# MaxAir_Smart_Home_Gateway_WT21-ET01-v095.net
KiCad netlist of a schematic drawn in EAGLE
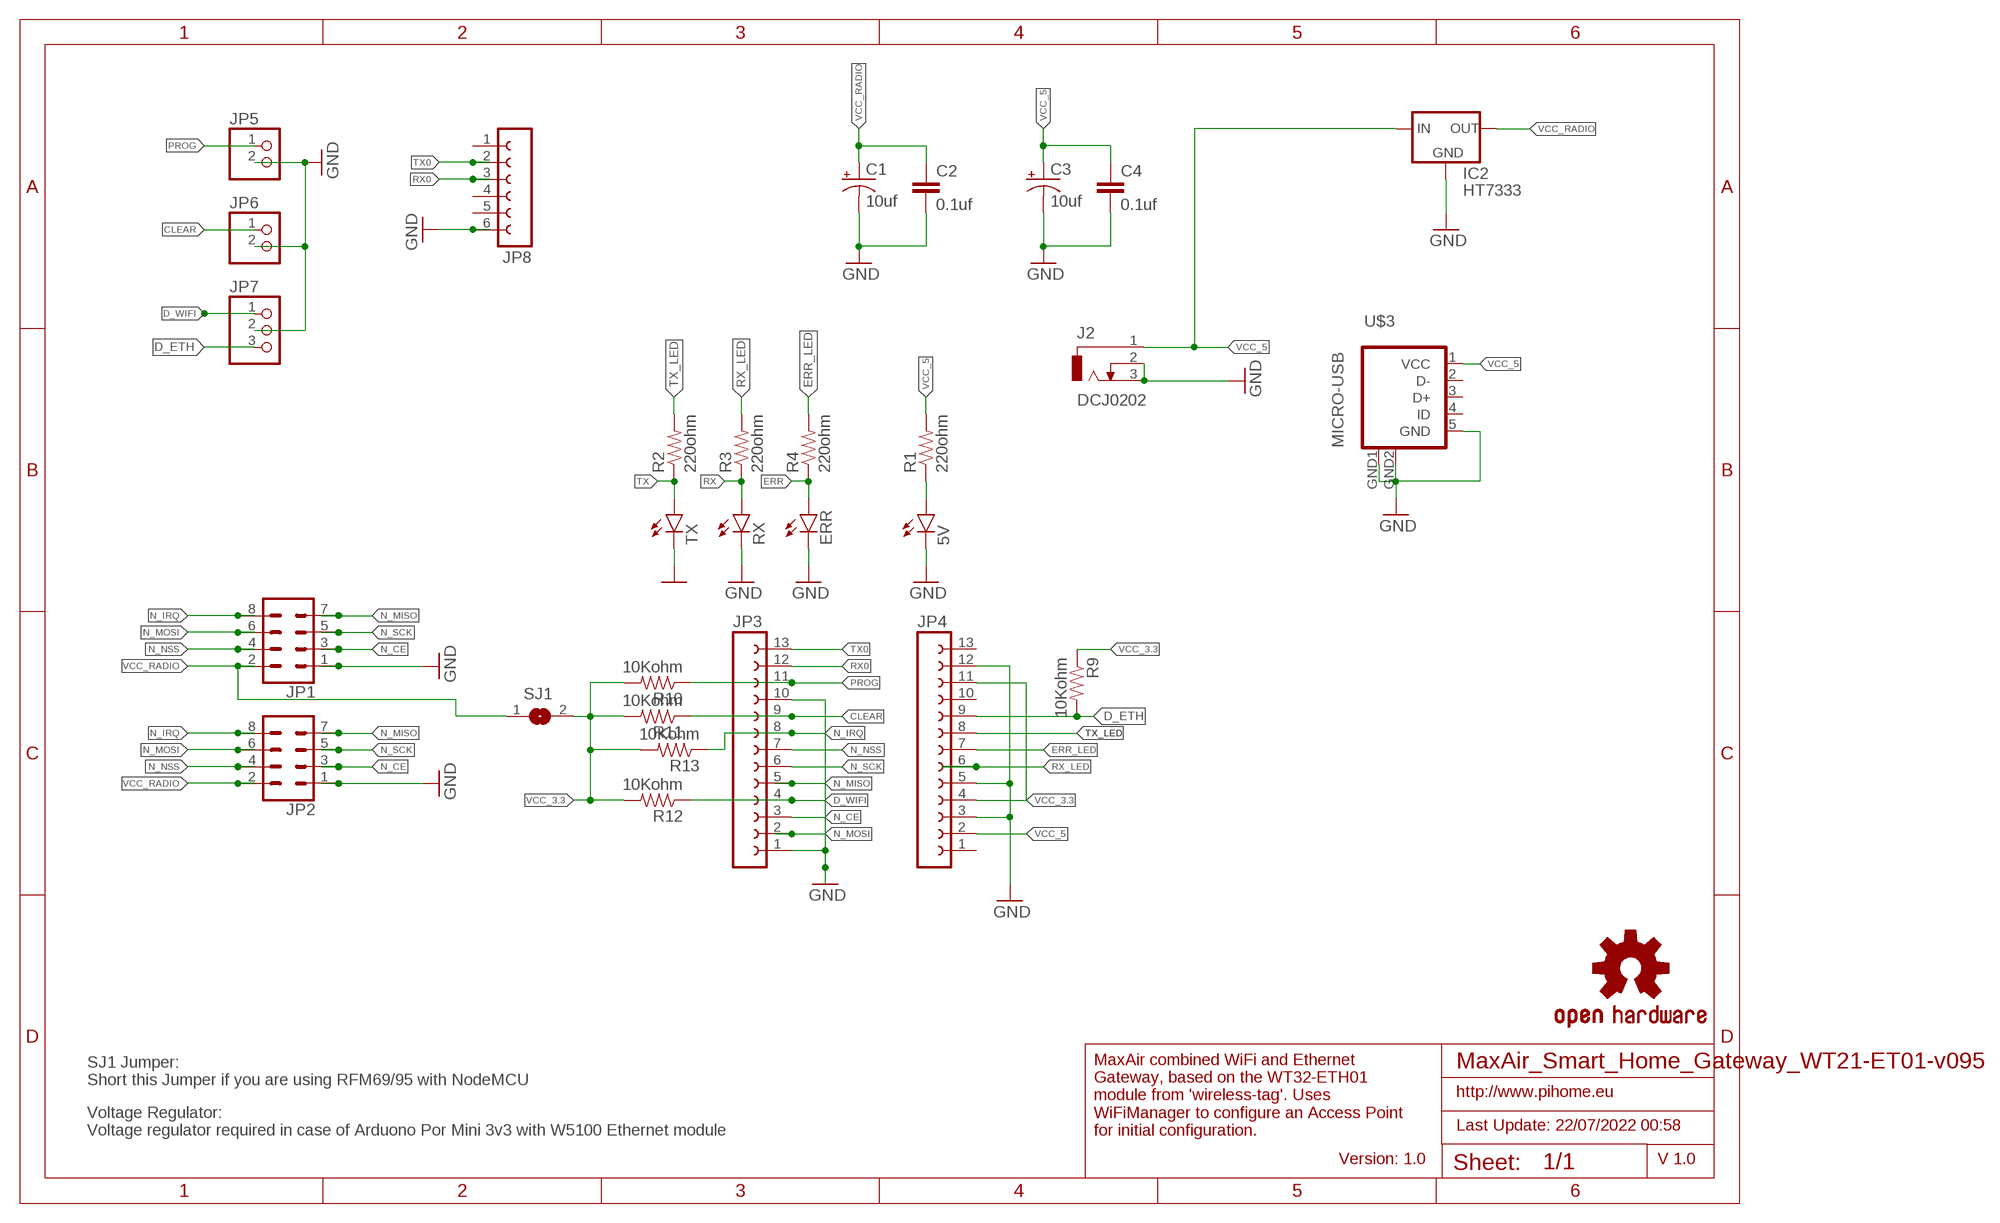
[diagram p0: schematic, sheet 1]

(export (version "E")
  (design (tool "Eeschema 10.0.6"))
  (components
    (comp (ref "5V")
      (value "LED3MM")
      (footprint "eagle-import:LED3MM")
      (libsource (lib "eagle-import") (part "LED3MM"))
    )
    (comp (ref "C1")
      (value "10uf")
      (footprint "eagle-import:CPOL-RADIAL-10UF-25V-KIT")
      (libsource (lib "eagle-import") (part "10UF-25V-20%(PTH)KIT"))
    )
    (comp (ref "C2")
      (value "0.1uf")
      (footprint "eagle-import:CAP-PTH-SMALL-KIT")
      (libsource (lib "eagle-import") (part "0.1UF-50V-20%(PTH)KIT-EZ"))
    )
    (comp (ref "C3")
      (value "10uf")
      (footprint "eagle-import:CPOL-RADIAL-10UF-25V-KIT")
      (libsource (lib "eagle-import") (part "10UF-25V-20%(PTH)KIT"))
    )
    (comp (ref "C4")
      (value "0.1uf")
      (footprint "eagle-import:CAP-PTH-SMALL-KIT")
      (libsource (lib "eagle-import") (part "0.1UF-50V-20%(PTH)KIT-EZ"))
    )
    (comp (ref "ERR")
      (value "LED3MM")
      (footprint "eagle-import:LED3MM")
      (libsource (lib "eagle-import") (part "LED3MM"))
    )
    (comp (ref "IC2")
      (value "HT7333")
      (footprint "eagle-import:SOT-89")
      (libsource (lib "eagle-import") (part "HT7333"))
    )
    (comp (ref "J2")
      (value "DCJ0202")
      (footprint "eagle-import:DCJ0202")
      (libsource (lib "eagle-import") (part "DCJ0202"))
    )
    (comp (ref "JP1")
      (value "CONN_04X2")
      (footprint "eagle-import:2X4")
      (libsource (lib "eagle-import") (part "CONN_04X2"))
    )
    (comp (ref "JP2")
      (value "CONN_04X2")
      (footprint "eagle-import:2X4")
      (libsource (lib "eagle-import") (part "CONN_04X2"))
    )
    (comp (ref "JP3")
      (value "FE13-1")
      (footprint "eagle-import:FE13")
      (libsource (lib "eagle-import") (part "FE13-1"))
    )
    (comp (ref "JP4")
      (value "FE13-1")
      (footprint "eagle-import:FE13")
      (libsource (lib "eagle-import") (part "FE13-1"))
    )
    (comp (ref "JP5")
      (value "PINHD-1X2")
      (footprint "eagle-import:1X02")
      (libsource (lib "eagle-import") (part "PINHD-1X2"))
    )
    (comp (ref "JP6")
      (value "PINHD-1X2")
      (footprint "eagle-import:1X02")
      (libsource (lib "eagle-import") (part "PINHD-1X2"))
    )
    (comp (ref "JP7")
      (value "PINHD-1X3")
      (footprint "eagle-import:1X03")
      (libsource (lib "eagle-import") (part "PINHD-1X3"))
    )
    (comp (ref "JP8")
      (value "FE06-1")
      (footprint "eagle-import:FE06")
      (libsource (lib "eagle-import") (part "FE06-1"))
    )
    (comp (ref "LOGO1")
      (value "OSHW-LOGOMINI")
      (footprint "eagle-import:OSHW-LOGO-MINI")
      (libsource (lib "eagle-import") (part "OSHW-LOGOMINI"))
    )
    (comp (ref "R1")
      (value "220ohm")
      (footprint "eagle-import:AXIAL-0.3")
      (libsource (lib "eagle-import") (part "RESISTORAXIAL-0.3"))
    )
    (comp (ref "R2")
      (value "220ohm")
      (footprint "eagle-import:AXIAL-0.3")
      (libsource (lib "eagle-import") (part "RESISTORAXIAL-0.3"))
    )
    (comp (ref "R3")
      (value "220ohm")
      (footprint "eagle-import:AXIAL-0.3")
      (libsource (lib "eagle-import") (part "RESISTORAXIAL-0.3"))
    )
    (comp (ref "R4")
      (value "220ohm")
      (footprint "eagle-import:AXIAL-0.3")
      (libsource (lib "eagle-import") (part "RESISTORAXIAL-0.3"))
    )
    (comp (ref "R9")
      (value "10Kohm")
      (footprint "eagle-import:AXIAL-0.3")
      (libsource (lib "eagle-import") (part "RESISTORAXIAL-0.3"))
    )
    (comp (ref "R10")
      (value "10Kohm")
      (footprint "eagle-import:AXIAL-0.3")
      (libsource (lib "eagle-import") (part "RESISTORAXIAL-0.3"))
    )
    (comp (ref "R11")
      (value "10Kohm")
      (footprint "eagle-import:AXIAL-0.3")
      (libsource (lib "eagle-import") (part "RESISTORAXIAL-0.3"))
    )
    (comp (ref "R12")
      (value "10Kohm")
      (footprint "eagle-import:AXIAL-0.3")
      (libsource (lib "eagle-import") (part "RESISTORAXIAL-0.3"))
    )
    (comp (ref "R13")
      (value "10Kohm")
      (footprint "eagle-import:AXIAL-0.3")
      (libsource (lib "eagle-import") (part "RESISTORAXIAL-0.3"))
    )
    (comp (ref "RX")
      (value "LED3MM")
      (footprint "eagle-import:LED3MM")
      (libsource (lib "eagle-import") (part "LED3MM"))
    )
    (comp (ref "SJ1") (value "SJ") (footprint "eagle-import:SJ") (libsource (lib "eagle-import") (part "SJ")))
    (comp (ref "TX")
      (value "LED3MM")
      (footprint "eagle-import:LED3MM")
      (libsource (lib "eagle-import") (part "LED3MM"))
    )
    (comp (ref "U$3")
      (value "MICRO-USB")
      (footprint "eagle-import:MICRO-USB")
      (libsource (lib "eagle-import") (part "MICRO-USB"))
    )
  )
  (nets
    (net (code "1") (name "CLEAR") (class "Default")
      (node (ref "JP3") (pin "9") (pinfunction "9_9") (pintype "passive"))
      (node (ref "JP6") (pin "1") (pinfunction "1_1") (pintype "passive"))
      (node (ref "R11") (pin "P$1") (pinfunction "1_P$1") (pintype "passive"))
    )
    (net (code "2") (name "D_ETH") (class "Default")
      (node (ref "JP4") (pin "9") (pinfunction "9_9") (pintype "passive"))
      (node (ref "JP7") (pin "3") (pinfunction "3_3") (pintype "passive"))
      (node (ref "R9") (pin "P$2") (pinfunction "2_P$2") (pintype "passive"))
    )
    (net (code "3") (name "D_WIFI") (class "Default")
      (node (ref "JP3") (pin "4") (pinfunction "4_4") (pintype "passive"))
      (node (ref "JP7") (pin "1") (pinfunction "1_1") (pintype "passive"))
      (node (ref "R12") (pin "P$1") (pinfunction "1_P$1") (pintype "passive"))
    )
    (net (code "4") (name "ERR") (class "Default")
      (node (ref "ERR") (pin "A") (pinfunction "A_A") (pintype "passive"))
      (node (ref "R4") (pin "P$1") (pinfunction "1_P$1") (pintype "passive"))
    )
    (net (code "5") (name "ERR_LED") (class "Default")
      (node (ref "JP4") (pin "7") (pinfunction "7_7") (pintype "passive"))
      (node (ref "R4") (pin "P$2") (pinfunction "2_P$2") (pintype "passive"))
    )
    (net (code "6") (name "GND") (class "Default")
      (node (ref "5V") (pin "K") (pinfunction "C_K") (pintype "passive"))
      (node (ref "C1") (pin "2") (pinfunction "-_2") (pintype "passive"))
      (node (ref "C2") (pin "2") (pinfunction "2_2") (pintype "passive"))
      (node (ref "C3") (pin "2") (pinfunction "-_2") (pintype "passive"))
      (node (ref "C4") (pin "2") (pinfunction "2_2") (pintype "passive"))
      (node (ref "ERR") (pin "K") (pinfunction "C_K") (pintype "passive"))
      (node (ref "IC2") (pin "2") (pinfunction "GND_2") (pintype "input"))
      (node (ref "J2") (pin "2") (pinfunction "2_2") (pintype "passive"))
      (node (ref "J2") (pin "3") (pinfunction "3_3") (pintype "passive"))
      (node (ref "JP1") (pin "1") (pinfunction "1_1") (pintype "passive"))
      (node (ref "JP2") (pin "1") (pinfunction "1_1") (pintype "passive"))
      (node (ref "JP3") (pin "1") (pinfunction "1_1") (pintype "passive"))
      (node (ref "JP3") (pin "10") (pinfunction "10_10") (pintype "passive"))
      (node (ref "JP4") (pin "12") (pinfunction "12_12") (pintype "passive"))
      (node (ref "JP4") (pin "3") (pinfunction "3_3") (pintype "passive"))
      (node (ref "JP4") (pin "5") (pinfunction "5_5") (pintype "passive"))
      (node (ref "JP5") (pin "2") (pinfunction "2_2") (pintype "passive"))
      (node (ref "JP6") (pin "2") (pinfunction "2_2") (pintype "passive"))
      (node (ref "JP7") (pin "2") (pinfunction "2_2") (pintype "passive"))
      (node (ref "JP8") (pin "6") (pinfunction "6_6") (pintype "passive"))
      (node (ref "RX") (pin "K") (pinfunction "C_K") (pintype "passive"))
      (node (ref "TX") (pin "K") (pinfunction "C_K") (pintype "passive"))
      (node (ref "U$3") (pin "5") (pinfunction "GND_5") (pintype "power_in"))
      (node (ref "U$3") (pin "GND1") (pinfunction "GND_GND1") (pintype "power_in"))
      (node (ref "U$3") (pin "GND2") (pinfunction "GND_GND2") (pintype "power_in"))
    )
    (net (code "7") (name "N_CE") (class "Default")
      (node (ref "JP1") (pin "3") (pinfunction "3_3") (pintype "passive"))
      (node (ref "JP2") (pin "3") (pinfunction "3_3") (pintype "passive"))
      (node (ref "JP3") (pin "3") (pinfunction "3_3") (pintype "passive"))
    )
    (net (code "8") (name "N_IRQ") (class "Default")
      (node (ref "JP1") (pin "8") (pinfunction "8_8") (pintype "passive"))
      (node (ref "JP2") (pin "8") (pinfunction "8_8") (pintype "passive"))
      (node (ref "JP3") (pin "8") (pinfunction "8_8") (pintype "passive"))
      (node (ref "R13") (pin "P$1") (pinfunction "1_P$1") (pintype "passive"))
    )
    (net (code "9") (name "N_MISO") (class "Default")
      (node (ref "JP1") (pin "7") (pinfunction "7_7") (pintype "passive"))
      (node (ref "JP2") (pin "7") (pinfunction "7_7") (pintype "passive"))
      (node (ref "JP3") (pin "5") (pinfunction "5_5") (pintype "passive"))
    )
    (net (code "10") (name "N_MOSI") (class "Default")
      (node (ref "JP1") (pin "6") (pinfunction "6_6") (pintype "passive"))
      (node (ref "JP2") (pin "6") (pinfunction "6_6") (pintype "passive"))
      (node (ref "JP3") (pin "2") (pinfunction "2_2") (pintype "passive"))
    )
    (net (code "11") (name "N_NSS") (class "Default")
      (node (ref "JP1") (pin "4") (pinfunction "4_4") (pintype "passive"))
      (node (ref "JP2") (pin "4") (pinfunction "4_4") (pintype "passive"))
      (node (ref "JP3") (pin "7") (pinfunction "7_7") (pintype "passive"))
    )
    (net (code "12") (name "N_SCK") (class "Default")
      (node (ref "JP1") (pin "5") (pinfunction "5_5") (pintype "passive"))
      (node (ref "JP2") (pin "5") (pinfunction "5_5") (pintype "passive"))
      (node (ref "JP3") (pin "6") (pinfunction "6_6") (pintype "passive"))
    )
    (net (code "13") (name "Net-(R1-1)") (class "Default")
      (node (ref "5V") (pin "A") (pinfunction "A_A") (pintype "passive"))
      (node (ref "R1") (pin "P$1") (pinfunction "1_P$1") (pintype "passive"))
    )
    (net (code "14") (name "PROG") (class "Default")
      (node (ref "JP3") (pin "11") (pinfunction "11_11") (pintype "passive"))
      (node (ref "JP5") (pin "1") (pinfunction "1_1") (pintype "passive"))
      (node (ref "R10") (pin "P$1") (pinfunction "1_P$1") (pintype "passive"))
    )
    (net (code "15") (name "RX") (class "Default")
      (node (ref "R3") (pin "P$1") (pinfunction "1_P$1") (pintype "passive"))
      (node (ref "RX") (pin "A") (pinfunction "A_A") (pintype "passive"))
    )
    (net (code "16") (name "RX0") (class "Default")
      (node (ref "JP3") (pin "12") (pinfunction "12_12") (pintype "passive"))
      (node (ref "JP8") (pin "3") (pinfunction "3_3") (pintype "passive"))
    )
    (net (code "17") (name "RX_LED") (class "Default")
      (node (ref "JP4") (pin "6") (pinfunction "6_6") (pintype "passive"))
      (node (ref "R3") (pin "P$2") (pinfunction "2_P$2") (pintype "passive"))
    )
    (net (code "18") (name "TX") (class "Default")
      (node (ref "R2") (pin "P$1") (pinfunction "1_P$1") (pintype "passive"))
      (node (ref "TX") (pin "A") (pinfunction "A_A") (pintype "passive"))
    )
    (net (code "19") (name "TX0") (class "Default")
      (node (ref "JP3") (pin "13") (pinfunction "13_13") (pintype "passive"))
      (node (ref "JP8") (pin "2") (pinfunction "2_2") (pintype "passive"))
    )
    (net (code "20") (name "TX_LED") (class "Default")
      (node (ref "JP4") (pin "8") (pinfunction "8_8") (pintype "passive"))
      (node (ref "R2") (pin "P$2") (pinfunction "2_P$2") (pintype "passive"))
    )
    (net (code "21") (name "VCC_3.3") (class "Default")
      (node (ref "JP4") (pin "11") (pinfunction "11_11") (pintype "passive"))
      (node (ref "JP4") (pin "4") (pinfunction "4_4") (pintype "passive"))
      (node (ref "R10") (pin "P$2") (pinfunction "2_P$2") (pintype "passive"))
      (node (ref "R11") (pin "P$2") (pinfunction "2_P$2") (pintype "passive"))
      (node (ref "R12") (pin "P$2") (pinfunction "2_P$2") (pintype "passive"))
      (node (ref "R13") (pin "P$2") (pinfunction "2_P$2") (pintype "passive"))
      (node (ref "R9") (pin "P$1") (pinfunction "1_P$1") (pintype "passive"))
      (node (ref "SJ1") (pin "2") (pinfunction "2_2") (pintype "passive"))
    )
    (net (code "22") (name "VCC_5") (class "Default")
      (node (ref "C3") (pin "1") (pinfunction "+_1") (pintype "passive"))
      (node (ref "C4") (pin "1") (pinfunction "1_1") (pintype "passive"))
      (node (ref "IC2") (pin "3") (pinfunction "IN_3") (pintype "input"))
      (node (ref "IC2") (pin "4") (pinfunction "IN_4") (pintype "input"))
      (node (ref "J2") (pin "1") (pinfunction "1_1") (pintype "passive"))
      (node (ref "JP4") (pin "2") (pinfunction "2_2") (pintype "passive"))
      (node (ref "R1") (pin "P$2") (pinfunction "2_P$2") (pintype "passive"))
      (node (ref "U$3") (pin "1") (pinfunction "VCC_1") (pintype "power_in"))
    )
    (net (code "23") (name "VCC_RADIO") (class "Default")
      (node (ref "C1") (pin "1") (pinfunction "+_1") (pintype "passive"))
      (node (ref "C2") (pin "1") (pinfunction "1_1") (pintype "passive"))
      (node (ref "IC2") (pin "1") (pinfunction "OUT_1") (pintype "passive"))
      (node (ref "JP1") (pin "2") (pinfunction "2_2") (pintype "passive"))
      (node (ref "JP2") (pin "2") (pinfunction "2_2") (pintype "passive"))
      (node (ref "SJ1") (pin "1") (pinfunction "1_1") (pintype "passive"))
    )
    (net (code "24") (name "unconnected-(JP4-Pad1)") (class "Default")
      (node (ref "JP4") (pin "1") (pinfunction "1_1") (pintype "passive"))
    )
    (net (code "25") (name "unconnected-(JP4-Pad10)") (class "Default")
      (node (ref "JP4") (pin "10") (pinfunction "10_10") (pintype "passive"))
    )
    (net (code "26") (name "unconnected-(JP4-Pad13)") (class "Default")
      (node (ref "JP4") (pin "13") (pinfunction "13_13") (pintype "passive"))
    )
    (net (code "27") (name "unconnected-(JP8-Pad1)") (class "Default")
      (node (ref "JP8") (pin "1") (pinfunction "1_1") (pintype "passive"))
    )
    (net (code "28") (name "unconnected-(JP8-Pad4)") (class "Default")
      (node (ref "JP8") (pin "4") (pinfunction "4_4") (pintype "passive"))
    )
    (net (code "29") (name "unconnected-(JP8-Pad5)") (class "Default")
      (node (ref "JP8") (pin "5") (pinfunction "5_5") (pintype "passive"))
    )
    (net (code "30") (name "unconnected-(U$3-D+-Pad3)") (class "Default")
      (node (ref "U$3") (pin "3") (pinfunction "D+_3") (pintype "bidirectional"))
    )
    (net (code "31") (name "unconnected-(U$3-D--Pad2)") (class "Default")
      (node (ref "U$3") (pin "2") (pinfunction "D-_2") (pintype "bidirectional"))
    )
    (net (code "32") (name "unconnected-(U$3-ID-Pad4)") (class "Default")
      (node (ref "U$3") (pin "4") (pinfunction "ID_4") (pintype "bidirectional"))
    )
  )
)
